# Mini_Oval.net
KiCad netlist of a schematic drawn in EAGLE
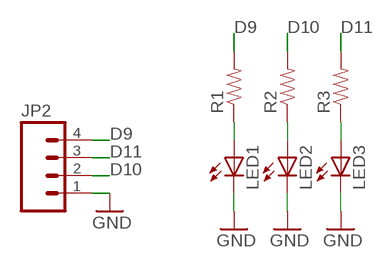
[diagram p0: schematic, sheet 1]

(export (version "E")
  (design (tool "Eeschema 10.0.6"))
  (components
    (comp (ref "JP2")
      (value "M04PTH")
      (footprint "eagle-import:1X04")
      (libsource (lib "eagle-import") (part "M04PTH"))
    )
    (comp (ref "LED1")
      (value "LEDOVAL")
      (footprint "eagle-import:LED-OVAL")
      (libsource (lib "eagle-import") (part "LEDOVAL"))
    )
    (comp (ref "LED2")
      (value "LEDOVAL")
      (footprint "eagle-import:LED-OVAL")
      (libsource (lib "eagle-import") (part "LEDOVAL"))
    )
    (comp (ref "LED3")
      (value "LEDOVAL")
      (footprint "eagle-import:LED-OVAL")
      (libsource (lib "eagle-import") (part "LEDOVAL"))
    )
    (comp (ref "R1")
      (value "RESISTORAXIAL-0.3")
      (footprint "eagle-import:AXIAL-0.3")
      (libsource (lib "eagle-import") (part "RESISTORAXIAL-0.3"))
    )
    (comp (ref "R2")
      (value "RESISTORAXIAL-0.3")
      (footprint "eagle-import:AXIAL-0.3")
      (libsource (lib "eagle-import") (part "RESISTORAXIAL-0.3"))
    )
    (comp (ref "R3")
      (value "RESISTORAXIAL-0.3")
      (footprint "eagle-import:AXIAL-0.3")
      (libsource (lib "eagle-import") (part "RESISTORAXIAL-0.3"))
    )
  )
  (nets
    (net (code "1") (name "/D9") (class "Default")
      (node (ref "JP2") (pin "4") (pinfunction "4_4") (pintype "passive"))
      (node (ref "R1") (pin "P$2") (pinfunction "2_P$2") (pintype "passive"))
    )
    (net (code "2") (name "/D10") (class "Default")
      (node (ref "JP2") (pin "2") (pinfunction "2_2") (pintype "passive"))
      (node (ref "R2") (pin "P$2") (pinfunction "2_P$2") (pintype "passive"))
    )
    (net (code "3") (name "/D11") (class "Default")
      (node (ref "JP2") (pin "3") (pinfunction "3_3") (pintype "passive"))
      (node (ref "R3") (pin "P$2") (pinfunction "2_P$2") (pintype "passive"))
    )
    (net (code "4") (name "GND") (class "Default")
      (node (ref "JP2") (pin "1") (pinfunction "1_1") (pintype "passive"))
      (node (ref "LED1") (pin "CATHODE") (pinfunction "C_CATHODE") (pintype "passive"))
      (node (ref "LED2") (pin "CATHODE") (pinfunction "C_CATHODE") (pintype "passive"))
      (node (ref "LED3") (pin "CATHODE") (pinfunction "C_CATHODE") (pintype "passive"))
    )
    (net (code "5") (name "Net-(LED1-A)") (class "Default")
      (node (ref "LED1") (pin "ANODE") (pinfunction "A_ANODE") (pintype "passive"))
      (node (ref "R1") (pin "P$1") (pinfunction "1_P$1") (pintype "passive"))
    )
    (net (code "6") (name "Net-(LED2-A)") (class "Default")
      (node (ref "LED2") (pin "ANODE") (pinfunction "A_ANODE") (pintype "passive"))
      (node (ref "R2") (pin "P$1") (pinfunction "1_P$1") (pintype "passive"))
    )
    (net (code "7") (name "Net-(LED3-A)") (class "Default")
      (node (ref "LED3") (pin "ANODE") (pinfunction "A_ANODE") (pintype "passive"))
      (node (ref "R3") (pin "P$1") (pinfunction "1_P$1") (pintype "passive"))
    )
  )
)
